# Comunica_o_RS232.net
KiCad netlist of a schematic drawn in EAGLE
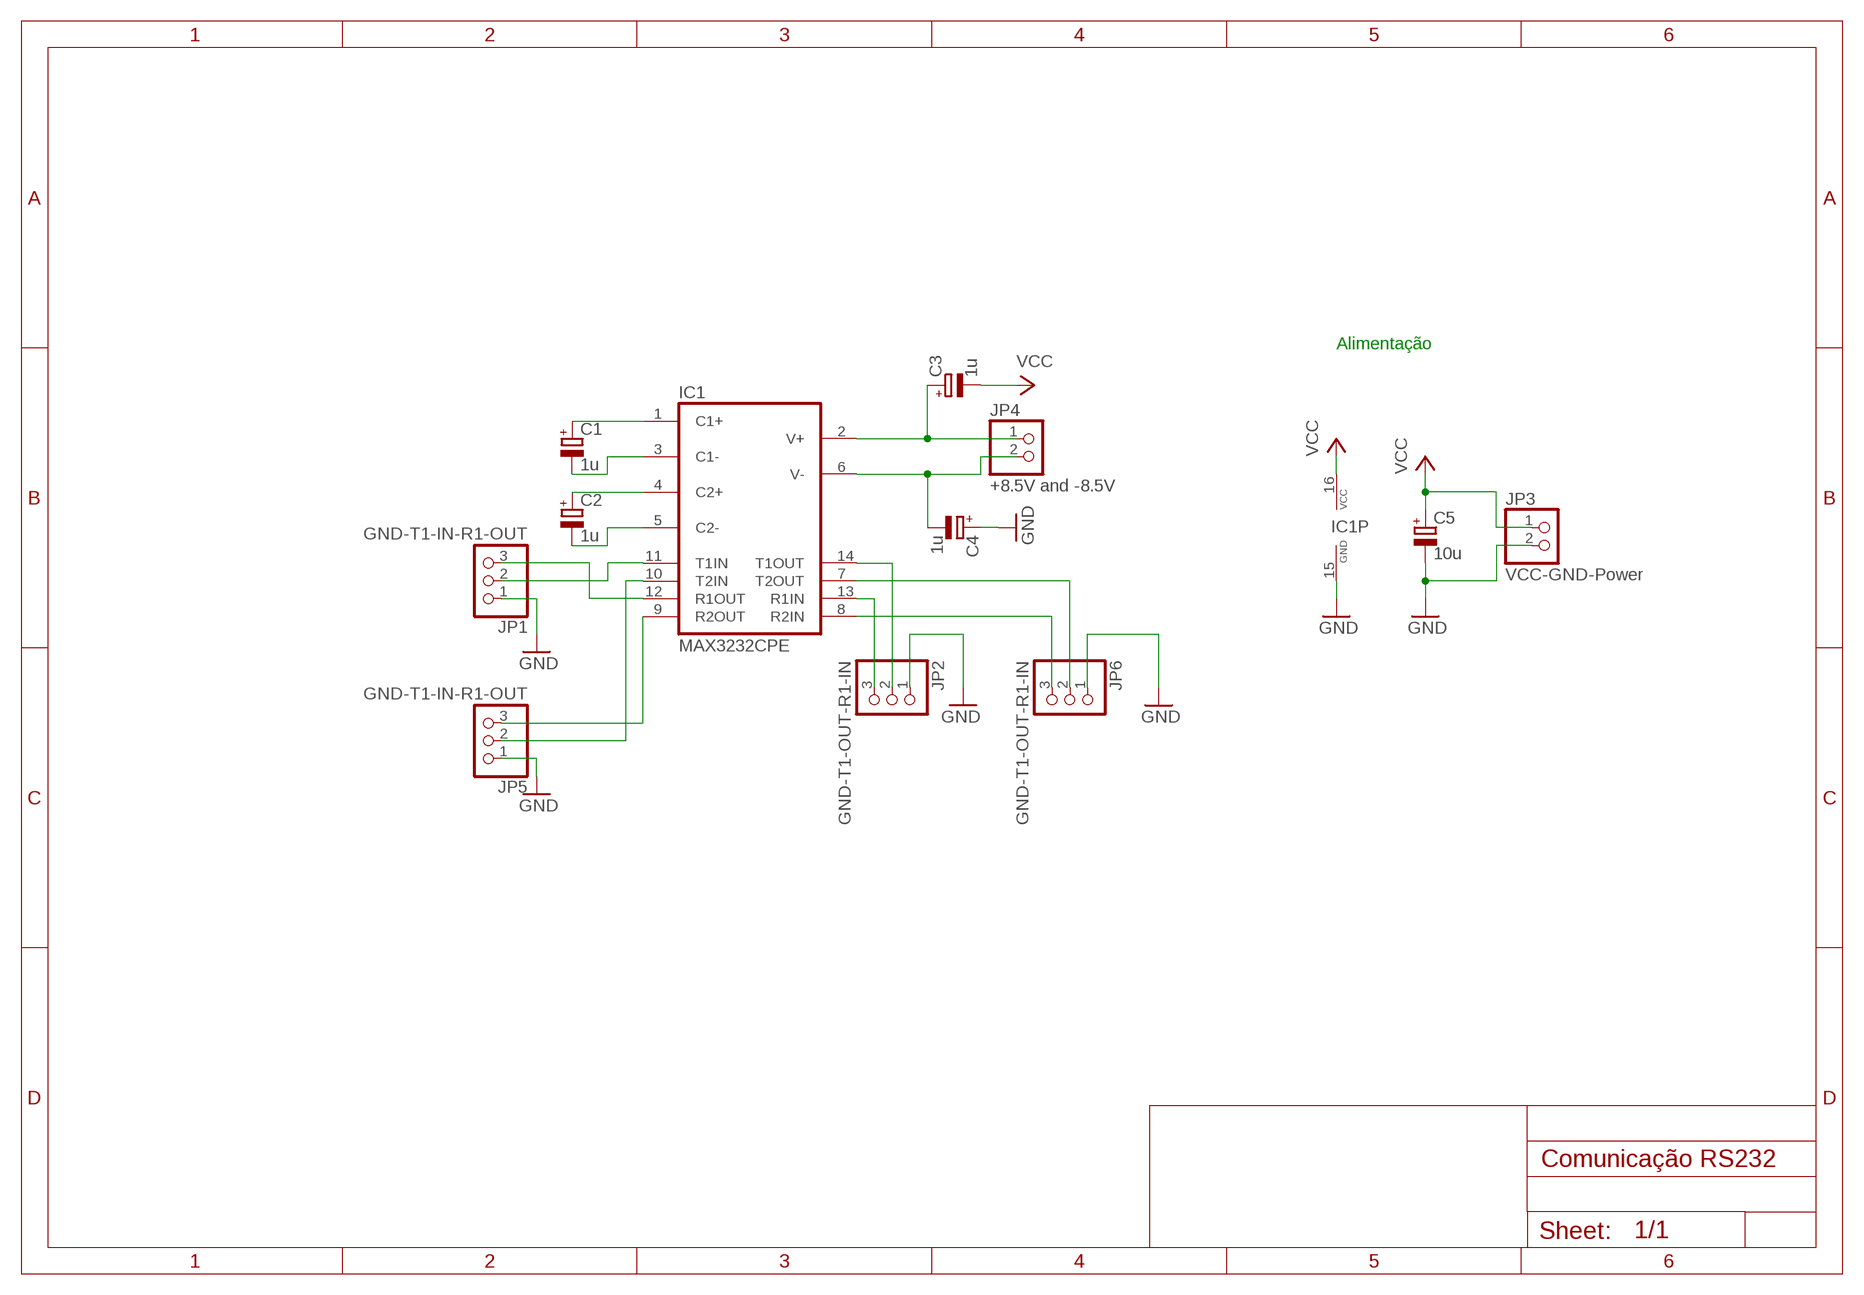
[diagram p0: schematic, sheet 1]

(export (version "E")
  (design (tool "Eeschema 10.0.6"))
  (components
    (comp (ref "C1")
      (value "1u")
      (footprint "eagle-import:E2,5-5")
      (libsource (lib "eagle-import") (part "CPOL-EUE2.5-5"))
    )
    (comp (ref "C2")
      (value "1u")
      (footprint "eagle-import:E2,5-5")
      (libsource (lib "eagle-import") (part "CPOL-EUE2.5-5"))
    )
    (comp (ref "C3")
      (value "1u")
      (footprint "eagle-import:E2,5-5")
      (libsource (lib "eagle-import") (part "CPOL-EUE2.5-5"))
    )
    (comp (ref "C4")
      (value "1u")
      (footprint "eagle-import:E2,5-5")
      (libsource (lib "eagle-import") (part "CPOL-EUE2.5-5"))
    )
    (comp (ref "C5")
      (value "10u")
      (footprint "eagle-import:E2,5-5")
      (libsource (lib "eagle-import") (part "CPOL-EUE2.5-5"))
    )
    (comp (ref "IC1")
      (value "MAX3232CPE")
      (footprint "eagle-import:DIL16")
      (fields (field (name "MF") "MAXIM") (field (name "MPN") "MAX3232CPE+"))
      (libsource (lib "eagle-import") (part "MAX3232PEC"))
    )
    (comp (ref "JP1")
      (value "GND-T1-IN-R1-OUT")
      (footprint "eagle-import:1X03")
      (libsource (lib "eagle-import") (part "PINHD-1X3"))
    )
    (comp (ref "JP2")
      (value "GND-T1-OUT-R1-IN")
      (footprint "eagle-import:1X03")
      (libsource (lib "eagle-import") (part "PINHD-1X3"))
    )
    (comp (ref "JP3")
      (value "VCC-GND-Power")
      (footprint "eagle-import:1X02")
      (libsource (lib "eagle-import") (part "PINHD-1X2"))
    )
    (comp (ref "JP4")
      (value "+8.5V and -8.5V")
      (footprint "eagle-import:1X02")
      (libsource (lib "eagle-import") (part "PINHD-1X2"))
    )
    (comp (ref "JP5")
      (value "GND-T1-IN-R1-OUT")
      (footprint "eagle-import:1X03")
      (libsource (lib "eagle-import") (part "PINHD-1X3"))
    )
    (comp (ref "JP6")
      (value "GND-T1-OUT-R1-IN")
      (footprint "eagle-import:1X03")
      (libsource (lib "eagle-import") (part "PINHD-1X3"))
    )
  )
  (nets
    (net (code "1") (name "GND") (class "Default")
      (node (ref "C4") (pin "+") (pinfunction "+_+") (pintype "passive"))
      (node (ref "C5") (pin "-") (pinfunction "-_-") (pintype "passive"))
      (node (ref "IC1") (pin "15") (pinfunction "GND_15") (pintype "power_in"))
      (node (ref "JP1") (pin "1") (pinfunction "1_1") (pintype "passive"))
      (node (ref "JP2") (pin "1") (pinfunction "1_1") (pintype "passive"))
      (node (ref "JP3") (pin "2") (pinfunction "2_2") (pintype "passive"))
      (node (ref "JP5") (pin "1") (pinfunction "1_1") (pintype "passive"))
      (node (ref "JP6") (pin "1") (pinfunction "1_1") (pintype "passive"))
    )
    (net (code "2") (name "Net-(IC1A-C1+)") (class "Default")
      (node (ref "C1") (pin "+") (pinfunction "+_+") (pintype "passive"))
      (node (ref "IC1") (pin "1") (pinfunction "C1+_1") (pintype "bidirectional"))
    )
    (net (code "3") (name "Net-(IC1A-C1-)") (class "Default")
      (node (ref "C1") (pin "-") (pinfunction "-_-") (pintype "passive"))
      (node (ref "IC1") (pin "3") (pinfunction "C1-_3") (pintype "bidirectional"))
    )
    (net (code "4") (name "Net-(IC1A-C2+)") (class "Default")
      (node (ref "C2") (pin "+") (pinfunction "+_+") (pintype "passive"))
      (node (ref "IC1") (pin "4") (pinfunction "C2+_4") (pintype "bidirectional"))
    )
    (net (code "5") (name "Net-(IC1A-C2-)") (class "Default")
      (node (ref "C2") (pin "-") (pinfunction "-_-") (pintype "passive"))
      (node (ref "IC1") (pin "5") (pinfunction "C2-_5") (pintype "bidirectional"))
    )
    (net (code "6") (name "Net-(IC1A-R1IN)") (class "Default")
      (node (ref "IC1") (pin "13") (pinfunction "R1IN_13") (pintype "input"))
      (node (ref "JP2") (pin "3") (pinfunction "3_3") (pintype "passive"))
    )
    (net (code "7") (name "Net-(IC1A-R1OUT)") (class "Default")
      (node (ref "IC1") (pin "12") (pinfunction "R1OUT_12") (pintype "output"))
      (node (ref "JP1") (pin "3") (pinfunction "3_3") (pintype "passive"))
    )
    (net (code "8") (name "Net-(IC1A-R2IN)") (class "Default")
      (node (ref "IC1") (pin "8") (pinfunction "R2IN_8") (pintype "input"))
      (node (ref "JP6") (pin "3") (pinfunction "3_3") (pintype "passive"))
    )
    (net (code "9") (name "Net-(IC1A-R2OUT)") (class "Default")
      (node (ref "IC1") (pin "9") (pinfunction "R2OUT_9") (pintype "output"))
      (node (ref "JP5") (pin "3") (pinfunction "3_3") (pintype "passive"))
    )
    (net (code "10") (name "Net-(IC1A-T1IN)") (class "Default")
      (node (ref "IC1") (pin "11") (pinfunction "T1IN_11") (pintype "input"))
      (node (ref "JP1") (pin "2") (pinfunction "2_2") (pintype "passive"))
    )
    (net (code "11") (name "Net-(IC1A-T1OUT)") (class "Default")
      (node (ref "IC1") (pin "14") (pinfunction "T1OUT_14") (pintype "output"))
      (node (ref "JP2") (pin "2") (pinfunction "2_2") (pintype "passive"))
    )
    (net (code "12") (name "Net-(IC1A-T2IN)") (class "Default")
      (node (ref "IC1") (pin "10") (pinfunction "T2IN_10") (pintype "input"))
      (node (ref "JP5") (pin "2") (pinfunction "2_2") (pintype "passive"))
    )
    (net (code "13") (name "Net-(IC1A-T2OUT)") (class "Default")
      (node (ref "IC1") (pin "7") (pinfunction "T2OUT_7") (pintype "output"))
      (node (ref "JP6") (pin "2") (pinfunction "2_2") (pintype "passive"))
    )
    (net (code "14") (name "Net-(IC1A-V+)") (class "Default")
      (node (ref "C3") (pin "+") (pinfunction "+_+") (pintype "passive"))
      (node (ref "IC1") (pin "2") (pinfunction "V+_2") (pintype "bidirectional"))
      (node (ref "JP4") (pin "1") (pinfunction "1_1") (pintype "passive"))
    )
    (net (code "15") (name "Net-(IC1A-V-)") (class "Default")
      (node (ref "C4") (pin "-") (pinfunction "-_-") (pintype "passive"))
      (node (ref "IC1") (pin "6") (pinfunction "V-_6") (pintype "bidirectional"))
      (node (ref "JP4") (pin "2") (pinfunction "2_2") (pintype "passive"))
    )
    (net (code "16") (name "VCC") (class "Default")
      (node (ref "C3") (pin "-") (pinfunction "-_-") (pintype "passive"))
      (node (ref "C5") (pin "+") (pinfunction "+_+") (pintype "passive"))
      (node (ref "IC1") (pin "16") (pinfunction "VCC_16") (pintype "power_in"))
      (node (ref "JP3") (pin "1") (pinfunction "1_1") (pintype "passive"))
    )
  )
)
